# button.net
KiCad netlist of a schematic drawn in EAGLE
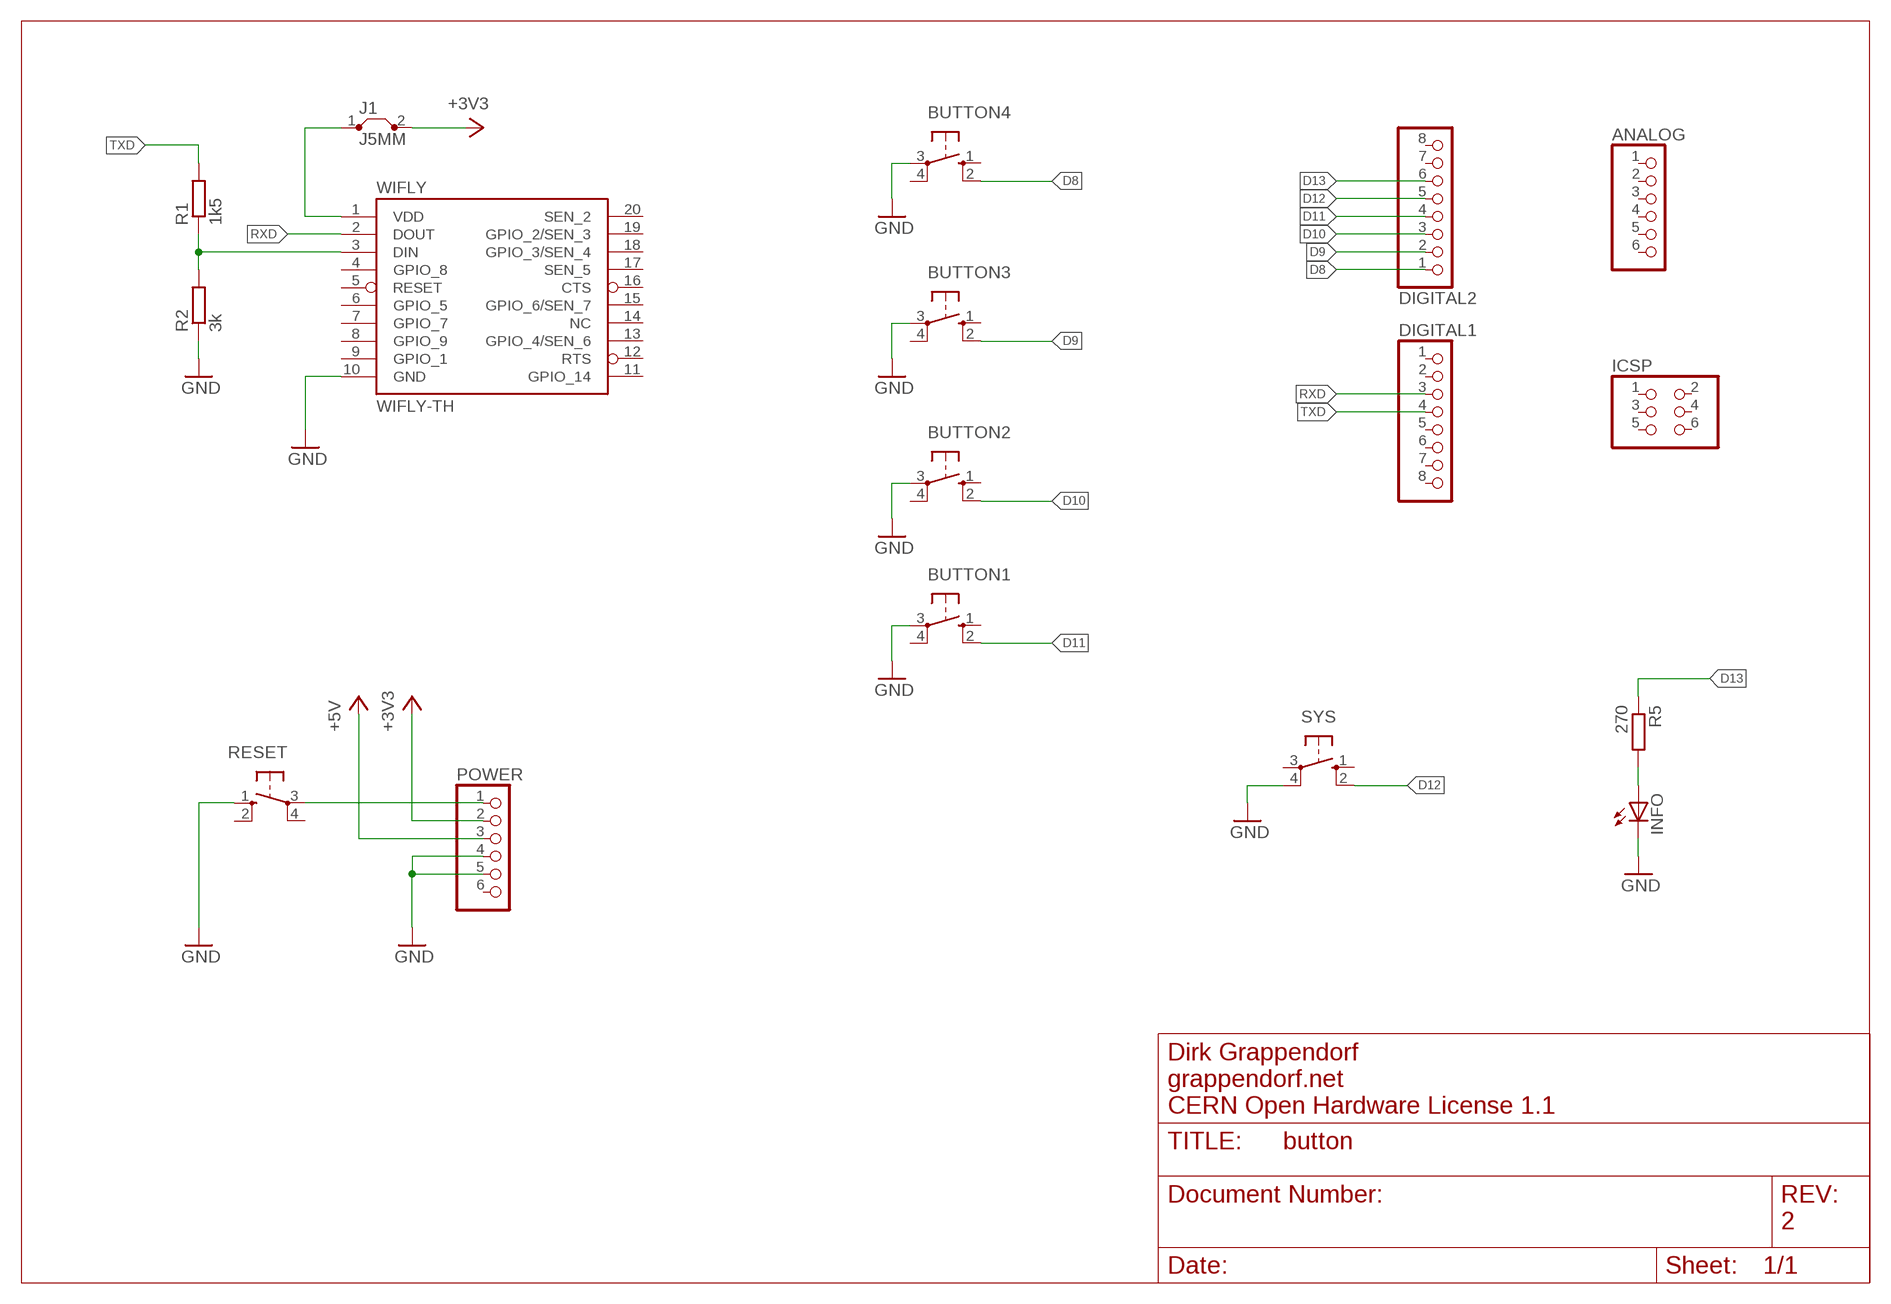
[diagram p0: schematic, sheet 1]

(export (version "E")
  (design (tool "Eeschema 10.0.6"))
  (components
    (comp (ref "ANALOG")
      (value "PINHD-1X6")
      (footprint "eagle-import:1X06")
      (libsource (lib "eagle-import") (part "PINHD-1X6"))
    )
    (comp (ref "BUTTON1")
      (value "10-XX")
      (footprint "eagle-import:B3F-10XX")
      (libsource (lib "eagle-import") (part "10-XX"))
    )
    (comp (ref "BUTTON2")
      (value "10-XX")
      (footprint "eagle-import:B3F-10XX")
      (libsource (lib "eagle-import") (part "10-XX"))
    )
    (comp (ref "BUTTON3")
      (value "10-XX")
      (footprint "eagle-import:B3F-10XX")
      (libsource (lib "eagle-import") (part "10-XX"))
    )
    (comp (ref "BUTTON4")
      (value "10-XX")
      (footprint "eagle-import:B3F-10XX")
      (libsource (lib "eagle-import") (part "10-XX"))
    )
    (comp (ref "DIGITAL1")
      (value "PINHD-1X8TH")
      (footprint "eagle-import:1X08-TH")
      (libsource (lib "eagle-import") (part "PINHD-1X8TH"))
    )
    (comp (ref "DIGITAL2")
      (value "PINHD-1X8_2.54")
      (footprint "eagle-import:1X08")
      (libsource (lib "eagle-import") (part "PINHD-1X8_2.54"))
    )
    (comp (ref "ICSP")
      (value "PINHD-2X3")
      (footprint "eagle-import:2X03")
      (libsource (lib "eagle-import") (part "PINHD-2X3"))
    )
    (comp (ref "INFO")
      (value "LED3MM")
      (footprint "eagle-import:LED3MM")
      (libsource (lib "eagle-import") (part "LED3MM"))
    )
    (comp (ref "J1")
      (value "J5MM")
      (footprint "eagle-import:05")
      (libsource (lib "eagle-import") (part "J5MM"))
    )
    (comp (ref "POWER")
      (value "PINHD-1X6_2.54")
      (footprint "eagle-import:1X06")
      (libsource (lib "eagle-import") (part "PINHD-1X6_2.54"))
    )
    (comp (ref "R1")
      (value "1k5")
      (footprint "eagle-import:0204_7")
      (libsource (lib "eagle-import") (part "R-EU_0204/7"))
    )
    (comp (ref "R2")
      (value "3k")
      (footprint "eagle-import:0204_7")
      (libsource (lib "eagle-import") (part "R-EU_0204/7"))
    )
    (comp (ref "R5")
      (value "270")
      (footprint "eagle-import:0204_7")
      (libsource (lib "eagle-import") (part "R-EU_0204/7"))
    )
    (comp (ref "RESET")
      (value "10-XX")
      (footprint "eagle-import:B3F-10XX")
      (libsource (lib "eagle-import") (part "10-XX"))
    )
    (comp (ref "SYS")
      (value "10-XX")
      (footprint "eagle-import:B3F-10XX")
      (libsource (lib "eagle-import") (part "10-XX"))
    )
    (comp (ref "WIFLY")
      (value "WIFLY-TH")
      (footprint "eagle-import:WIFLY-TH")
      (libsource (lib "eagle-import") (part "WIFLY-TH"))
    )
  )
  (nets
    (net (code "1") (name "+3V3") (class "Default")
      (node (ref "J1") (pin "2") (pinfunction "2_2") (pintype "passive"))
      (node (ref "POWER") (pin "2") (pinfunction "2_2") (pintype "passive"))
    )
    (net (code "2") (name "+5V") (class "Default")
      (node (ref "POWER") (pin "3") (pinfunction "3_3") (pintype "passive"))
    )
    (net (code "3") (name "D8") (class "Default")
      (node (ref "BUTTON4") (pin "2") (pinfunction "S1_2") (pintype "passive"))
      (node (ref "DIGITAL2") (pin "1") (pinfunction "1_1") (pintype "passive"))
    )
    (net (code "4") (name "D9") (class "Default")
      (node (ref "BUTTON3") (pin "2") (pinfunction "S1_2") (pintype "passive"))
      (node (ref "DIGITAL2") (pin "2") (pinfunction "2_2") (pintype "passive"))
    )
    (net (code "5") (name "D10") (class "Default")
      (node (ref "BUTTON2") (pin "2") (pinfunction "S1_2") (pintype "passive"))
      (node (ref "DIGITAL2") (pin "3") (pinfunction "3_3") (pintype "passive"))
    )
    (net (code "6") (name "D11") (class "Default")
      (node (ref "BUTTON1") (pin "2") (pinfunction "S1_2") (pintype "passive"))
      (node (ref "DIGITAL2") (pin "4") (pinfunction "4_4") (pintype "passive"))
    )
    (net (code "7") (name "D12") (class "Default")
      (node (ref "DIGITAL2") (pin "5") (pinfunction "5_5") (pintype "passive"))
      (node (ref "SYS") (pin "2") (pinfunction "S1_2") (pintype "passive"))
    )
    (net (code "8") (name "D13") (class "Default")
      (node (ref "DIGITAL2") (pin "6") (pinfunction "6_6") (pintype "passive"))
      (node (ref "R5") (pin "1") (pinfunction "1_1") (pintype "passive"))
    )
    (net (code "9") (name "GND") (class "Default")
      (node (ref "BUTTON1") (pin "3") (pinfunction "P_3") (pintype "passive"))
      (node (ref "BUTTON2") (pin "3") (pinfunction "P_3") (pintype "passive"))
      (node (ref "BUTTON3") (pin "3") (pinfunction "P_3") (pintype "passive"))
      (node (ref "BUTTON4") (pin "3") (pinfunction "P_3") (pintype "passive"))
      (node (ref "INFO") (pin "K") (pinfunction "C_K") (pintype "passive"))
      (node (ref "POWER") (pin "4") (pinfunction "4_4") (pintype "passive"))
      (node (ref "POWER") (pin "5") (pinfunction "5_5") (pintype "passive"))
      (node (ref "R2") (pin "1") (pinfunction "1_1") (pintype "passive"))
      (node (ref "RESET") (pin "1") (pinfunction "S_1") (pintype "passive"))
      (node (ref "SYS") (pin "4") (pinfunction "P1_4") (pintype "passive"))
      (node (ref "WIFLY") (pin "10") (pinfunction "GND_10") (pintype "power_in"))
    )
    (net (code "10") (name "Net-(INFO-PadA)") (class "Default")
      (node (ref "INFO") (pin "A") (pinfunction "A_A") (pintype "passive"))
      (node (ref "R5") (pin "2") (pinfunction "2_2") (pintype "passive"))
    )
    (net (code "11") (name "Net-(RESET-P)") (class "Default")
      (node (ref "POWER") (pin "1") (pinfunction "1_1") (pintype "passive"))
      (node (ref "RESET") (pin "3") (pinfunction "P_3") (pintype "passive"))
    )
    (net (code "12") (name "Net-(WIFLY-DIN)") (class "Default")
      (node (ref "R1") (pin "1") (pinfunction "1_1") (pintype "passive"))
      (node (ref "R2") (pin "2") (pinfunction "2_2") (pintype "passive"))
      (node (ref "WIFLY") (pin "3") (pinfunction "DIN_3") (pintype "input"))
    )
    (net (code "13") (name "Net-(WIFLY-VDD)") (class "Default")
      (node (ref "J1") (pin "1") (pinfunction "1_1") (pintype "passive"))
      (node (ref "WIFLY") (pin "1") (pinfunction "VDD_1") (pintype "power_in"))
    )
    (net (code "14") (name "RXD") (class "Default")
      (node (ref "DIGITAL1") (pin "3") (pinfunction "3_3") (pintype "passive"))
      (node (ref "WIFLY") (pin "2") (pinfunction "DOUT_2") (pintype "output"))
    )
    (net (code "15") (name "TXD") (class "Default")
      (node (ref "DIGITAL1") (pin "4") (pinfunction "4_4") (pintype "passive"))
      (node (ref "R1") (pin "2") (pinfunction "2_2") (pintype "passive"))
    )
    (net (code "16") (name "unconnected-(ANALOG-Pad1)") (class "Default")
      (node (ref "ANALOG") (pin "1") (pinfunction "1_1") (pintype "passive"))
    )
    (net (code "17") (name "unconnected-(ANALOG-Pad2)") (class "Default")
      (node (ref "ANALOG") (pin "2") (pinfunction "2_2") (pintype "passive"))
    )
    (net (code "18") (name "unconnected-(ANALOG-Pad3)") (class "Default")
      (node (ref "ANALOG") (pin "3") (pinfunction "3_3") (pintype "passive"))
    )
    (net (code "19") (name "unconnected-(ANALOG-Pad4)") (class "Default")
      (node (ref "ANALOG") (pin "4") (pinfunction "4_4") (pintype "passive"))
    )
    (net (code "20") (name "unconnected-(ANALOG-Pad5)") (class "Default")
      (node (ref "ANALOG") (pin "5") (pinfunction "5_5") (pintype "passive"))
    )
    (net (code "21") (name "unconnected-(ANALOG-Pad6)") (class "Default")
      (node (ref "ANALOG") (pin "6") (pinfunction "6_6") (pintype "passive"))
    )
    (net (code "22") (name "unconnected-(BUTTON1-P1-Pad4)") (class "Default")
      (node (ref "BUTTON1") (pin "4") (pinfunction "P1_4") (pintype "passive"))
    )
    (net (code "23") (name "unconnected-(BUTTON1-S-Pad1)") (class "Default")
      (node (ref "BUTTON1") (pin "1") (pinfunction "S_1") (pintype "passive"))
    )
    (net (code "24") (name "unconnected-(BUTTON2-P1-Pad4)") (class "Default")
      (node (ref "BUTTON2") (pin "4") (pinfunction "P1_4") (pintype "passive"))
    )
    (net (code "25") (name "unconnected-(BUTTON2-S-Pad1)") (class "Default")
      (node (ref "BUTTON2") (pin "1") (pinfunction "S_1") (pintype "passive"))
    )
    (net (code "26") (name "unconnected-(BUTTON3-P1-Pad4)") (class "Default")
      (node (ref "BUTTON3") (pin "4") (pinfunction "P1_4") (pintype "passive"))
    )
    (net (code "27") (name "unconnected-(BUTTON3-S-Pad1)") (class "Default")
      (node (ref "BUTTON3") (pin "1") (pinfunction "S_1") (pintype "passive"))
    )
    (net (code "28") (name "unconnected-(BUTTON4-P1-Pad4)") (class "Default")
      (node (ref "BUTTON4") (pin "4") (pinfunction "P1_4") (pintype "passive"))
    )
    (net (code "29") (name "unconnected-(BUTTON4-S-Pad1)") (class "Default")
      (node (ref "BUTTON4") (pin "1") (pinfunction "S_1") (pintype "passive"))
    )
    (net (code "30") (name "unconnected-(DIGITAL1-Pad1)") (class "Default")
      (node (ref "DIGITAL1") (pin "1") (pinfunction "1_1") (pintype "passive"))
    )
    (net (code "31") (name "unconnected-(DIGITAL1-Pad2)") (class "Default")
      (node (ref "DIGITAL1") (pin "2") (pinfunction "2_2") (pintype "passive"))
    )
    (net (code "32") (name "unconnected-(DIGITAL1-Pad5)") (class "Default")
      (node (ref "DIGITAL1") (pin "5") (pinfunction "5_5") (pintype "passive"))
    )
    (net (code "33") (name "unconnected-(DIGITAL1-Pad6)") (class "Default")
      (node (ref "DIGITAL1") (pin "6") (pinfunction "6_6") (pintype "passive"))
    )
    (net (code "34") (name "unconnected-(DIGITAL1-Pad7)") (class "Default")
      (node (ref "DIGITAL1") (pin "7") (pinfunction "7_7") (pintype "passive"))
    )
    (net (code "35") (name "unconnected-(DIGITAL1-Pad8)") (class "Default")
      (node (ref "DIGITAL1") (pin "8") (pinfunction "8_8") (pintype "passive"))
    )
    (net (code "36") (name "unconnected-(DIGITAL2-Pad7)") (class "Default")
      (node (ref "DIGITAL2") (pin "7") (pinfunction "7_7") (pintype "passive"))
    )
    (net (code "37") (name "unconnected-(DIGITAL2-Pad8)") (class "Default")
      (node (ref "DIGITAL2") (pin "8") (pinfunction "8_8") (pintype "passive"))
    )
    (net (code "38") (name "unconnected-(ICSP-Pad1)") (class "Default")
      (node (ref "ICSP") (pin "1") (pinfunction "1_1") (pintype "passive"))
    )
    (net (code "39") (name "unconnected-(ICSP-Pad2)") (class "Default")
      (node (ref "ICSP") (pin "2") (pinfunction "2_2") (pintype "passive"))
    )
    (net (code "40") (name "unconnected-(ICSP-Pad3)") (class "Default")
      (node (ref "ICSP") (pin "3") (pinfunction "3_3") (pintype "passive"))
    )
    (net (code "41") (name "unconnected-(ICSP-Pad4)") (class "Default")
      (node (ref "ICSP") (pin "4") (pinfunction "4_4") (pintype "passive"))
    )
    (net (code "42") (name "unconnected-(ICSP-Pad5)") (class "Default")
      (node (ref "ICSP") (pin "5") (pinfunction "5_5") (pintype "passive"))
    )
    (net (code "43") (name "unconnected-(ICSP-Pad6)") (class "Default")
      (node (ref "ICSP") (pin "6") (pinfunction "6_6") (pintype "passive"))
    )
    (net (code "44") (name "unconnected-(POWER-Pad6)") (class "Default")
      (node (ref "POWER") (pin "6") (pinfunction "6_6") (pintype "passive"))
    )
    (net (code "45") (name "unconnected-(RESET-P1-Pad4)") (class "Default")
      (node (ref "RESET") (pin "4") (pinfunction "P1_4") (pintype "passive"))
    )
    (net (code "46") (name "unconnected-(RESET-S1-Pad2)") (class "Default")
      (node (ref "RESET") (pin "2") (pinfunction "S1_2") (pintype "passive"))
    )
    (net (code "47") (name "unconnected-(SYS-P-Pad3)") (class "Default")
      (node (ref "SYS") (pin "3") (pinfunction "P_3") (pintype "passive"))
    )
    (net (code "48") (name "unconnected-(SYS-S-Pad1)") (class "Default")
      (node (ref "SYS") (pin "1") (pinfunction "S_1") (pintype "passive"))
    )
    (net (code "49") (name "unconnected-(WIFLY-CTS-Pad16)") (class "Default")
      (node (ref "WIFLY") (pin "16") (pinfunction "CTS_16") (pintype "input"))
    )
    (net (code "50") (name "unconnected-(WIFLY-GPIO_1-Pad9)") (class "Default")
      (node (ref "WIFLY") (pin "9") (pinfunction "GPIO_1_9") (pintype "bidirectional"))
    )
    (net (code "51") (name "unconnected-(WIFLY-GPIO_2{slash}SEN_3-Pad19)") (class "Default")
      (node (ref "WIFLY") (pin "19") (pinfunction "GPIO_2/SEN_3_19") (pintype "bidirectional"))
    )
    (net (code "52") (name "unconnected-(WIFLY-GPIO_3{slash}SEN_4-Pad18)") (class "Default")
      (node (ref "WIFLY") (pin "18") (pinfunction "GPIO_3/SEN_4_18") (pintype "bidirectional"))
    )
    (net (code "53") (name "unconnected-(WIFLY-GPIO_4{slash}SEN_6-Pad13)") (class "Default")
      (node (ref "WIFLY") (pin "13") (pinfunction "GPIO_4/SEN_6_13") (pintype "bidirectional"))
    )
    (net (code "54") (name "unconnected-(WIFLY-GPIO_5-Pad6)") (class "Default")
      (node (ref "WIFLY") (pin "6") (pinfunction "GPIO_5_6") (pintype "bidirectional"))
    )
    (net (code "55") (name "unconnected-(WIFLY-GPIO_6{slash}SEN_7-Pad15)") (class "Default")
      (node (ref "WIFLY") (pin "15") (pinfunction "GPIO_6/SEN_7_15") (pintype "bidirectional"))
    )
    (net (code "56") (name "unconnected-(WIFLY-GPIO_7-Pad7)") (class "Default")
      (node (ref "WIFLY") (pin "7") (pinfunction "GPIO_7_7") (pintype "bidirectional"))
    )
    (net (code "57") (name "unconnected-(WIFLY-GPIO_8-Pad4)") (class "Default")
      (node (ref "WIFLY") (pin "4") (pinfunction "GPIO_8_4") (pintype "bidirectional"))
    )
    (net (code "58") (name "unconnected-(WIFLY-GPIO_9-Pad8)") (class "Default")
      (node (ref "WIFLY") (pin "8") (pinfunction "GPIO_9_8") (pintype "bidirectional"))
    )
    (net (code "59") (name "unconnected-(WIFLY-GPIO_14-Pad11)") (class "Default")
      (node (ref "WIFLY") (pin "11") (pinfunction "GPIO_14_11") (pintype "bidirectional"))
    )
    (net (code "60") (name "unconnected-(WIFLY-NC-Pad14)") (class "Default")
      (node (ref "WIFLY") (pin "14") (pinfunction "NC_14") (pintype "bidirectional"))
    )
    (net (code "61") (name "unconnected-(WIFLY-RESET-Pad5)") (class "Default")
      (node (ref "WIFLY") (pin "5") (pinfunction "RESET_5") (pintype "input"))
    )
    (net (code "62") (name "unconnected-(WIFLY-RTS-Pad12)") (class "Default")
      (node (ref "WIFLY") (pin "12") (pinfunction "RTS_12") (pintype "output"))
    )
    (net (code "63") (name "unconnected-(WIFLY-SEN_2-Pad20)") (class "Default")
      (node (ref "WIFLY") (pin "20") (pinfunction "SEN_2_20") (pintype "bidirectional"))
    )
    (net (code "64") (name "unconnected-(WIFLY-SEN_5-Pad17)") (class "Default")
      (node (ref "WIFLY") (pin "17") (pinfunction "SEN_5_17") (pintype "bidirectional"))
    )
  )
)
